# RTL_mPCIE.net
KiCad netlist of a schematic drawn in Altium Designer
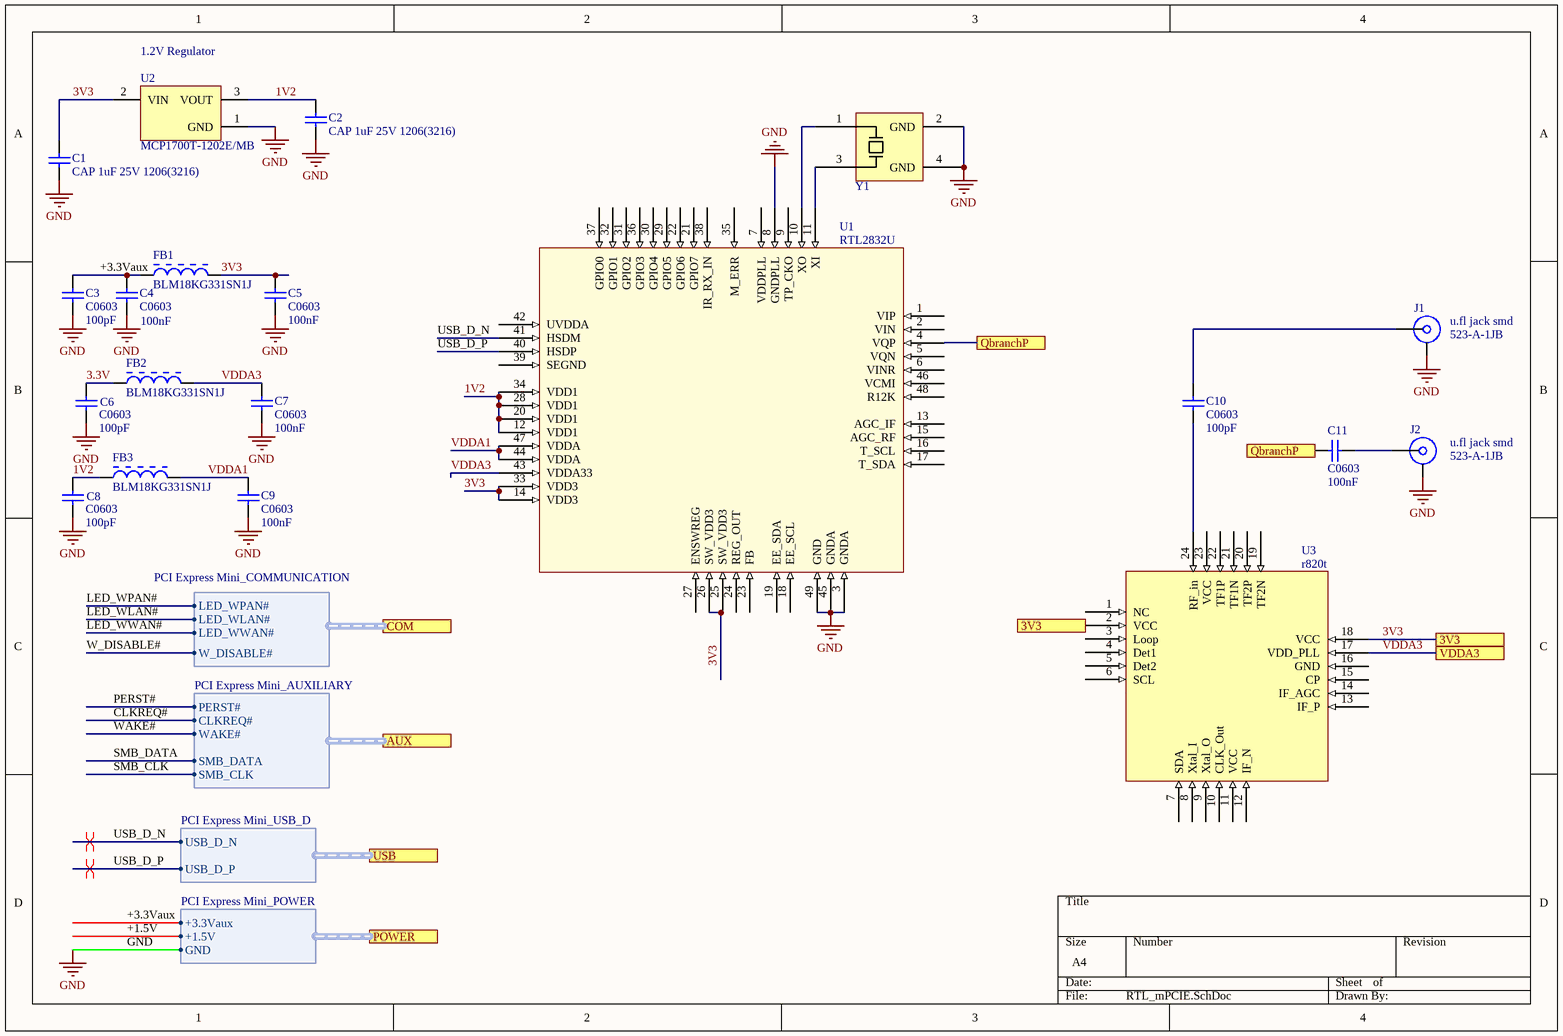
[diagram p0: RTL_mPCIE.SchDoc]

(export (version "E")
  (design (tool "Eeschema 10.0.6"))
  (components
    (comp (ref "C1")
      (value "CAP 1uF 25V 1206(3216)")
      (footprint "CAPC1206(3216)130_M")
      (description "CAP 1uF 25V ±10% 1206 (3216 Metric) Thickness 1.3mm SMD")
      (fields (field (name "TOLERANCE") "Â±10%"))
      (libsource (lib "Altium Content Vault") (part "CAP"))
    )
    (comp (ref "C2")
      (value "CAP 1uF 25V 1206(3216)")
      (footprint "CAPC1206(3216)130_M")
      (description "CAP 1uF 25V ±10% 1206 (3216 Metric) Thickness 1.3mm SMD")
      (fields (field (name "TOLERANCE") "Â±10%"))
      (libsource (lib "Altium Content Vault") (part "CAP"))
    )
    (comp (ref "C3")
      (value "C0603")
      (footprint "0603")
      (description "Ceramic Chip Capacitor - Standard")
      (fields (field (name "ALTIUM_VALUE") "100pF") (field (name "PUBLISHER") "Altium Limited"))
      (libsource (lib "KEMET Chip Capacitor") (part "C0603"))
    )
    (comp (ref "C4")
      (value "C0603")
      (footprint "0603")
      (description "Ceramic Chip Capacitor - Standard")
      (fields (field (name "ALTIUM_VALUE") "100nF") (field (name "PUBLISHER") "Altium Limited"))
      (libsource (lib "KEMET Chip Capacitor") (part "C0603"))
    )
    (comp (ref "C5")
      (value "C0603")
      (footprint "0603")
      (description "Ceramic Chip Capacitor - Standard")
      (fields (field (name "ALTIUM_VALUE") "100nF") (field (name "PUBLISHER") "Altium Limited"))
      (libsource (lib "KEMET Chip Capacitor") (part "C0603"))
    )
    (comp (ref "C6")
      (value "C0603")
      (footprint "0603")
      (description "Ceramic Chip Capacitor - Standard")
      (fields (field (name "ALTIUM_VALUE") "100pF") (field (name "PUBLISHER") "Altium Limited"))
      (libsource (lib "KEMET Chip Capacitor") (part "C0603"))
    )
    (comp (ref "C7")
      (value "C0603")
      (footprint "0603")
      (description "Ceramic Chip Capacitor - Standard")
      (fields (field (name "ALTIUM_VALUE") "100nF") (field (name "PUBLISHER") "Altium Limited"))
      (libsource (lib "KEMET Chip Capacitor") (part "C0603"))
    )
    (comp (ref "C8")
      (value "C0603")
      (footprint "0603")
      (description "Ceramic Chip Capacitor - Standard")
      (fields (field (name "ALTIUM_VALUE") "100pF") (field (name "PUBLISHER") "Altium Limited"))
      (libsource (lib "KEMET Chip Capacitor") (part "C0603"))
    )
    (comp (ref "C9")
      (value "C0603")
      (footprint "0603")
      (description "Ceramic Chip Capacitor - Standard")
      (fields (field (name "ALTIUM_VALUE") "100nF") (field (name "PUBLISHER") "Altium Limited"))
      (libsource (lib "KEMET Chip Capacitor") (part "C0603"))
    )
    (comp (ref "C10")
      (value "C0603")
      (footprint "0603")
      (description "Ceramic Chip Capacitor - Standard")
      (fields (field (name "ALTIUM_VALUE") "100pF") (field (name "PUBLISHER") "Altium Limited"))
      (libsource (lib "KEMET Chip Capacitor") (part "C0603"))
    )
    (comp (ref "C11")
      (value "C0603")
      (footprint "0603")
      (description "Ceramic Chip Capacitor - Standard")
      (fields (field (name "ALTIUM_VALUE") "100nF") (field (name "PUBLISHER") "Altium Limited"))
      (libsource (lib "KEMET Chip Capacitor") (part "C0603"))
    )
    (comp (ref "FB1")
      (value "BLM18KG331SN1J")
      (footprint "MURA-BLM18PG_KG-B25-CHIP-2_V1")
      (fields (field (name "MANUFACTURER") "Murata"))
      (libsource (lib "Altium Content Vault") (part "MURA-FB-2"))
    )
    (comp (ref "FB2")
      (value "BLM18KG331SN1J")
      (footprint "MURA-BLM18PG_KG-B25-CHIP-2_V1")
      (fields (field (name "MANUFACTURER") "Murata"))
      (libsource (lib "Altium Content Vault") (part "MURA-FB-2"))
    )
    (comp (ref "FB3")
      (value "BLM18KG331SN1J")
      (footprint "MURA-BLM18PG_KG-B25-CHIP-2_V1")
      (fields (field (name "MANUFACTURER") "Murata"))
      (libsource (lib "Altium Content Vault") (part "MURA-FB-2"))
    )
    (comp (ref "J1")
      (value "u.fl jack smd")
      (footprint "U.FL jack")
      (fields (field (name "SUPPLIER PART NUMBER 1") "523-A-1JB"))
      (libsource (lib "ftg_lib") (part "u.fl connector, jack A-1JB"))
    )
    (comp (ref "J2")
      (value "u.fl jack smd")
      (footprint "U.FL jack")
      (fields (field (name "SUPPLIER PART NUMBER 1") "523-A-1JB"))
      (libsource (lib "ftg_lib") (part "u.fl connector, jack A-1JB"))
    )
    (comp (ref "U1")
      (value "RTL2832U")
      (footprint "QFN40P600X600X84_HS-49N")
      (description "RTL2832U DVB-T COFDM Demodulator + USB 2.0")
      (fields (field (name "MANUFACTURER") "Realtek") (field (name "PUBLISHER") "ftg"))
      (libsource (lib "ftg_lib") (part "RTL2832U"))
    )
    (comp (ref "U2")
      (value "MCP1700T-1202E/MB")
      (footprint "SOT-89-MB3_N")
      (description "Low Quiescent Current LDO, 3-Pin SOT-89, Extended Temperature, Tape and Reel")
      (libsource (lib "Altium Content Vault") (part "PM-LINEREG-MCP1700-IL3A"))
    )
    (comp (ref "U3")
      (value "r820t")
      (footprint "QFN50P400X400X85_HS-25N_r820t")
      (libsource (lib "ftg_lib") (part "r820t"))
    )
    (comp (ref "Y1")
      (value "Crystal")
      (footprint "Abracon_ABM11")
      (description "Crystal, 16MHz, 10pF, 4-SMD (2x1.6)")
      (fields
        (field (name "MANUFACTURER") "Abracon")
        (field (name "TOLERANCE") "20ppm")
        (field (name "AUTHOR") "JDS")
      )
      (libsource (lib "0084 - AR Display Board Rev2.1") (part "XTAL_0024"))
    )
  )
  (nets
    (net (code "8") (name "/+3.3Vaux") (class "Default")
      (node (ref "C3") (pin "2") (pinfunction "2_2") (pintype "passive"))
      (node (ref "C4") (pin "2") (pinfunction "2_2") (pintype "passive"))
      (node (ref "FB1") (pin "1") (pinfunction "1_1") (pintype "passive"))
    )
    (net (code "9") (name "/1V2") (class "Default")
      (node (ref "C2") (pin "2") (pinfunction "2_2") (pintype "passive"))
      (node (ref "C8") (pin "2") (pinfunction "2_2") (pintype "passive"))
      (node (ref "FB3") (pin "1") (pinfunction "1_1") (pintype "passive"))
      (node (ref "U1") (pin "12") (pinfunction "VDD1_12") (pintype "input"))
      (node (ref "U1") (pin "20") (pinfunction "VDD1_20") (pintype "input"))
      (node (ref "U1") (pin "28") (pinfunction "VDD1_28") (pintype "input"))
      (node (ref "U1") (pin "34") (pinfunction "VDD1_34") (pintype "input"))
      (node (ref "U2") (pin "3") (pinfunction "VOUT_3") (pintype "power_in"))
    )
    (net (code "10") (name "/3.3V") (class "Default")
      (node (ref "C6") (pin "2") (pinfunction "2_2") (pintype "passive"))
      (node (ref "FB2") (pin "1") (pinfunction "1_1") (pintype "passive"))
    )
    (net (code "11") (name "/3V3") (class "Default")
      (node (ref "C1") (pin "2") (pinfunction "2_2") (pintype "passive"))
      (node (ref "C5") (pin "2") (pinfunction "2_2") (pintype "passive"))
      (node (ref "FB1") (pin "2") (pinfunction "2_2") (pintype "passive"))
      (node (ref "U1") (pin "14") (pinfunction "VDD3_14") (pintype "input"))
      (node (ref "U1") (pin "25") (pinfunction "SW_VDD3_25") (pintype "input"))
      (node (ref "U1") (pin "26") (pinfunction "SW_VDD3_26") (pintype "input"))
      (node (ref "U1") (pin "33") (pinfunction "VDD3_33") (pintype "input"))
      (node (ref "U2") (pin "2") (pinfunction "VIN_2") (pintype "power_in"))
      (node (ref "U3") (pin "18") (pinfunction "VCC_18") (pintype "input"))
      (node (ref "U3") (pin "2") (pinfunction "VCC_2") (pintype "input"))
    )
    (net (code "17") (name "/QbranchP") (class "Default")
      (node (ref "C11") (pin "2") (pinfunction "2_2") (pintype "passive"))
      (node (ref "U1") (pin "4") (pinfunction "VQP_4") (pintype "input"))
    )
    (net (code "20") (name "/USB_D_N") (class "Default")
      (node (ref "U1") (pin "41") (pinfunction "HSDM_41") (pintype "input"))
    )
    (net (code "21") (name "/USB_D_P") (class "Default")
      (node (ref "U1") (pin "40") (pinfunction "HSDP_40") (pintype "input"))
    )
    (net (code "22") (name "/VDDA1") (class "Default")
      (node (ref "C9") (pin "2") (pinfunction "2_2") (pintype "passive"))
      (node (ref "FB3") (pin "2") (pinfunction "2_2") (pintype "passive"))
      (node (ref "U1") (pin "44") (pinfunction "VDDA_44") (pintype "input"))
      (node (ref "U1") (pin "47") (pinfunction "VDDA_47") (pintype "input"))
    )
    (net (code "23") (name "/VDDA3") (class "Default")
      (node (ref "C7") (pin "2") (pinfunction "2_2") (pintype "passive"))
      (node (ref "FB2") (pin "2") (pinfunction "2_2") (pintype "passive"))
      (node (ref "U1") (pin "43") (pinfunction "VDDA33_43") (pintype "input"))
      (node (ref "U3") (pin "17") (pinfunction "VDD_PLL_17") (pintype "input"))
    )
    (net (code "30") (name "GND") (class "Default")
      (node (ref "C1") (pin "1") (pinfunction "1_1") (pintype "passive"))
      (node (ref "C2") (pin "1") (pinfunction "1_1") (pintype "passive"))
      (node (ref "C3") (pin "1") (pinfunction "1_1") (pintype "passive"))
      (node (ref "C4") (pin "1") (pinfunction "1_1") (pintype "passive"))
      (node (ref "C5") (pin "1") (pinfunction "1_1") (pintype "passive"))
      (node (ref "C6") (pin "1") (pinfunction "1_1") (pintype "passive"))
      (node (ref "C7") (pin "1") (pinfunction "1_1") (pintype "passive"))
      (node (ref "C8") (pin "1") (pinfunction "1_1") (pintype "passive"))
      (node (ref "C9") (pin "1") (pinfunction "1_1") (pintype "passive"))
      (node (ref "J1") (pin "2") (pinfunction "2_2") (pintype "passive"))
      (node (ref "J2") (pin "2") (pinfunction "2_2") (pintype "passive"))
      (node (ref "U1") (pin "3") (pinfunction "GNDA_3") (pintype "input"))
      (node (ref "U1") (pin "45") (pinfunction "GNDA_45") (pintype "input"))
      (node (ref "U1") (pin "49") (pinfunction "GND_49") (pintype "input"))
      (node (ref "U1") (pin "8") (pinfunction "GNDPLL_8") (pintype "input"))
      (node (ref "U2") (pin "1") (pinfunction "GND_1") (pintype "power_in"))
      (node (ref "Y1") (pin "2") (pinfunction "GND_2") (pintype "passive"))
      (node (ref "Y1") (pin "4") (pinfunction "GND_4") (pintype "passive"))
    )
    (net (code "31") (name "Net-(C10-Pad2)") (class "Default")
      (node (ref "C10") (pin "2") (pinfunction "2_2") (pintype "passive"))
      (node (ref "J1") (pin "1") (pinfunction "1_1") (pintype "passive"))
    )
    (net (code "32") (name "Net-(C11-Pad1)") (class "Default")
      (node (ref "C11") (pin "1") (pinfunction "1_1") (pintype "passive"))
      (node (ref "J2") (pin "1") (pinfunction "1_1") (pintype "passive"))
    )
    (net (code "33") (name "Net-(U1-XI)") (class "Default")
      (node (ref "U1") (pin "11") (pinfunction "XI_11") (pintype "input"))
      (node (ref "Y1") (pin "3") (pinfunction "XTAL2_3") (pintype "passive"))
    )
    (net (code "34") (name "Net-(U1-XO)") (class "Default")
      (node (ref "U1") (pin "10") (pinfunction "XO_10") (pintype "input"))
      (node (ref "Y1") (pin "1") (pinfunction "XTAL1_1") (pintype "passive"))
    )
    (net (code "35") (name "Net-(U3-RF_in)") (class "Default")
      (node (ref "C10") (pin "1") (pinfunction "1_1") (pintype "passive"))
      (node (ref "U3") (pin "24") (pinfunction "RF_in_24") (pintype "input"))
    )
    (net (code "36") (name "unconnected-(U1-AGC_IF-Pad13)") (class "Default")
      (node (ref "U1") (pin "13") (pinfunction "AGC_IF_13") (pintype "input"))
    )
    (net (code "37") (name "unconnected-(U1-AGC_RF-Pad15)") (class "Default")
      (node (ref "U1") (pin "15") (pinfunction "AGC_RF_15") (pintype "input"))
    )
    (net (code "38") (name "unconnected-(U1-EE_SCL-Pad18)") (class "Default")
      (node (ref "U1") (pin "18") (pinfunction "EE_SCL_18") (pintype "input"))
    )
    (net (code "39") (name "unconnected-(U1-EE_SDA-Pad19)") (class "Default")
      (node (ref "U1") (pin "19") (pinfunction "EE_SDA_19") (pintype "input"))
    )
    (net (code "40") (name "unconnected-(U1-ENSWREG-Pad27)") (class "Default")
      (node (ref "U1") (pin "27") (pinfunction "ENSWREG_27") (pintype "input"))
    )
    (net (code "41") (name "unconnected-(U1-FB-Pad23)") (class "Default")
      (node (ref "U1") (pin "23") (pinfunction "FB_23") (pintype "input"))
    )
    (net (code "42") (name "unconnected-(U1-GPIO0-Pad37)") (class "Default")
      (node (ref "U1") (pin "37") (pinfunction "GPIO0_37") (pintype "input"))
    )
    (net (code "43") (name "unconnected-(U1-GPIO1-Pad32)") (class "Default")
      (node (ref "U1") (pin "32") (pinfunction "GPIO1_32") (pintype "input"))
    )
    (net (code "44") (name "unconnected-(U1-GPIO2-Pad31)") (class "Default")
      (node (ref "U1") (pin "31") (pinfunction "GPIO2_31") (pintype "input"))
    )
    (net (code "45") (name "unconnected-(U1-GPIO3-Pad36)") (class "Default")
      (node (ref "U1") (pin "36") (pinfunction "GPIO3_36") (pintype "input"))
    )
    (net (code "46") (name "unconnected-(U1-GPIO4-Pad30)") (class "Default")
      (node (ref "U1") (pin "30") (pinfunction "GPIO4_30") (pintype "input"))
    )
    (net (code "47") (name "unconnected-(U1-GPIO5-Pad29)") (class "Default")
      (node (ref "U1") (pin "29") (pinfunction "GPIO5_29") (pintype "input"))
    )
    (net (code "48") (name "unconnected-(U1-GPIO6-Pad22)") (class "Default")
      (node (ref "U1") (pin "22") (pinfunction "GPIO6_22") (pintype "input"))
    )
    (net (code "49") (name "unconnected-(U1-GPIO7-Pad21)") (class "Default")
      (node (ref "U1") (pin "21") (pinfunction "GPIO7_21") (pintype "input"))
    )
    (net (code "50") (name "unconnected-(U1-IR_RX_IN-Pad38)") (class "Default")
      (node (ref "U1") (pin "38") (pinfunction "IR_RX_IN_38") (pintype "input"))
    )
    (net (code "51") (name "unconnected-(U1-M_ERR-Pad35)") (class "Default")
      (node (ref "U1") (pin "35") (pinfunction "M_ERR_35") (pintype "input"))
    )
    (net (code "52") (name "unconnected-(U1-R12K-Pad48)") (class "Default")
      (node (ref "U1") (pin "48") (pinfunction "R12K_48") (pintype "input"))
    )
    (net (code "53") (name "unconnected-(U1-REG_OUT-Pad24)") (class "Default")
      (node (ref "U1") (pin "24") (pinfunction "REG_OUT_24") (pintype "input"))
    )
    (net (code "54") (name "unconnected-(U1-SEGND-Pad39)") (class "Default")
      (node (ref "U1") (pin "39") (pinfunction "SEGND_39") (pintype "input"))
    )
    (net (code "55") (name "unconnected-(U1-TP_CKO-Pad9)") (class "Default")
      (node (ref "U1") (pin "9") (pinfunction "TP_CKO_9") (pintype "input"))
    )
    (net (code "56") (name "unconnected-(U1-T_SCL-Pad16)") (class "Default")
      (node (ref "U1") (pin "16") (pinfunction "T_SCL_16") (pintype "input"))
    )
    (net (code "57") (name "unconnected-(U1-T_SDA-Pad17)") (class "Default")
      (node (ref "U1") (pin "17") (pinfunction "T_SDA_17") (pintype "input"))
    )
    (net (code "58") (name "unconnected-(U1-UVDDA-Pad42)") (class "Default")
      (node (ref "U1") (pin "42") (pinfunction "UVDDA_42") (pintype "input"))
    )
    (net (code "59") (name "unconnected-(U1-VCMI-Pad46)") (class "Default")
      (node (ref "U1") (pin "46") (pinfunction "VCMI_46") (pintype "input"))
    )
    (net (code "60") (name "unconnected-(U1-VDDPLL-Pad7)") (class "Default")
      (node (ref "U1") (pin "7") (pinfunction "VDDPLL_7") (pintype "input"))
    )
    (net (code "61") (name "unconnected-(U1-VIN-Pad2)") (class "Default")
      (node (ref "U1") (pin "2") (pinfunction "VIN_2") (pintype "input"))
    )
    (net (code "62") (name "unconnected-(U1-VINR-Pad6)") (class "Default")
      (node (ref "U1") (pin "6") (pinfunction "VINR_6") (pintype "input"))
    )
    (net (code "63") (name "unconnected-(U1-VIP-Pad1)") (class "Default")
      (node (ref "U1") (pin "1") (pinfunction "VIP_1") (pintype "input"))
    )
    (net (code "64") (name "unconnected-(U1-VQN-Pad5)") (class "Default")
      (node (ref "U1") (pin "5") (pinfunction "VQN_5") (pintype "input"))
    )
    (net (code "65") (name "unconnected-(U3-CLK_Out-Pad10)") (class "Default")
      (node (ref "U3") (pin "10") (pinfunction "CLK_Out_10") (pintype "input"))
    )
    (net (code "66") (name "unconnected-(U3-CP-Pad15)") (class "Default")
      (node (ref "U3") (pin "15") (pinfunction "CP_15") (pintype "input"))
    )
    (net (code "67") (name "unconnected-(U3-Det1-Pad4)") (class "Default")
      (node (ref "U3") (pin "4") (pinfunction "Det1_4") (pintype "input"))
    )
    (net (code "68") (name "unconnected-(U3-Det2-Pad5)") (class "Default")
      (node (ref "U3") (pin "5") (pinfunction "Det2_5") (pintype "input"))
    )
    (net (code "69") (name "unconnected-(U3-GND-Pad16)") (class "Default")
      (node (ref "U3") (pin "16") (pinfunction "GND_16") (pintype "input"))
    )
    (net (code "70") (name "unconnected-(U3-GND-Pad25)") (class "Default")
      (node (ref "U3") (pin "25") (pinfunction "GND_25") (pintype "power_in"))
    )
    (net (code "71") (name "unconnected-(U3-IF_AGC-Pad14)") (class "Default")
      (node (ref "U3") (pin "14") (pinfunction "IF_AGC_14") (pintype "input"))
    )
    (net (code "72") (name "unconnected-(U3-IF_N-Pad12)") (class "Default")
      (node (ref "U3") (pin "12") (pinfunction "IF_N_12") (pintype "input"))
    )
    (net (code "73") (name "unconnected-(U3-IF_P-Pad13)") (class "Default")
      (node (ref "U3") (pin "13") (pinfunction "IF_P_13") (pintype "input"))
    )
    (net (code "74") (name "unconnected-(U3-Loop-Pad3)") (class "Default")
      (node (ref "U3") (pin "3") (pinfunction "Loop_3") (pintype "input"))
    )
    (net (code "75") (name "unconnected-(U3-NC-Pad1)") (class "Default")
      (node (ref "U3") (pin "1") (pinfunction "NC_1") (pintype "input"))
    )
    (net (code "76") (name "unconnected-(U3-SCL-Pad6)") (class "Default")
      (node (ref "U3") (pin "6") (pinfunction "SCL_6") (pintype "input"))
    )
    (net (code "77") (name "unconnected-(U3-SDA-Pad7)") (class "Default")
      (node (ref "U3") (pin "7") (pinfunction "SDA_7") (pintype "input"))
    )
    (net (code "78") (name "unconnected-(U3-TF1N-Pad21)") (class "Default")
      (node (ref "U3") (pin "21") (pinfunction "TF1N_21") (pintype "input"))
    )
    (net (code "79") (name "unconnected-(U3-TF1P-Pad22)") (class "Default")
      (node (ref "U3") (pin "22") (pinfunction "TF1P_22") (pintype "input"))
    )
    (net (code "80") (name "unconnected-(U3-TF2N-Pad19)") (class "Default")
      (node (ref "U3") (pin "19") (pinfunction "TF2N_19") (pintype "input"))
    )
    (net (code "81") (name "unconnected-(U3-TF2P-Pad20)") (class "Default")
      (node (ref "U3") (pin "20") (pinfunction "TF2P_20") (pintype "input"))
    )
    (net (code "82") (name "unconnected-(U3-VCC-Pad11)") (class "Default")
      (node (ref "U3") (pin "11") (pinfunction "VCC_11") (pintype "input"))
    )
    (net (code "83") (name "unconnected-(U3-VCC-Pad23)") (class "Default")
      (node (ref "U3") (pin "23") (pinfunction "VCC_23") (pintype "input"))
    )
    (net (code "84") (name "unconnected-(U3-Xtal_I-Pad8)") (class "Default")
      (node (ref "U3") (pin "8") (pinfunction "Xtal_I_8") (pintype "input"))
    )
    (net (code "85") (name "unconnected-(U3-Xtal_O-Pad9)") (class "Default")
      (node (ref "U3") (pin "9") (pinfunction "Xtal_O_9") (pintype "input"))
    )
  )
)
